# Pressure_ADC.net
KiCad netlist of a schematic drawn in Altium Designer
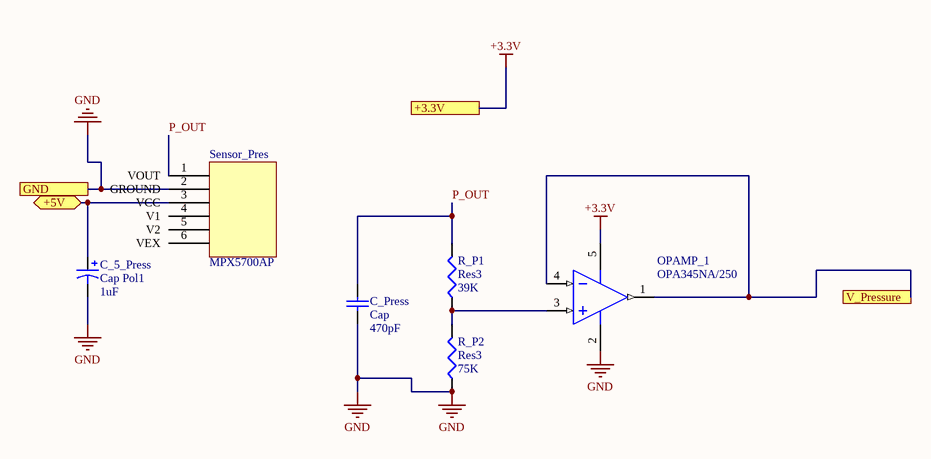
[diagram p0: Pressure ADC.SchDoc]

(export (version "E")
  (design (tool "Eeschema 10.0.6"))
  (components
    (comp (ref "C_5_Press")
      (value "Cap Pol1")
      (footprint "CAPR5-4X5")
      (description "Polarized Capacitor (Radial)")
      (fields (field (name "ALTIUM_VALUE") "1uF") (field (name "PUBLISHER") "Altium Limited"))
      (libsource (lib "Miscellaneous Devices") (part "Cap Pol1"))
    )
    (comp (ref "C_Press")
      (value "Cap")
      (footprint "3.2X1.6X1.1")
      (description "Capacitor")
      (fields (field (name "ALTIUM_VALUE") "470pF") (field (name "PUBLISHER") "Altium Limited"))
      (libsource (lib "Miscellaneous Devices") (part "Cap"))
    )
    (comp (ref "OPAMP_1")
      (value "OPA345NA/250")
      (footprint "TI-DBV5_N")
      (fields (field (name "MANUFACTURER") "Texas Instruments"))
      (libsource (lib "TI Amplifiers and Linear Operational Amplifier Precision Amplifier Part One") (part "OPA345NA/250"))
    )
    (comp (ref "R_P1")
      (value "Res3")
      (footprint "J1-0603")
      (description "Resistor")
      (fields (field (name "ALTIUM_VALUE") "39K") (field (name "PUBLISHER") "Altium Limited"))
      (libsource (lib "Miscellaneous Devices") (part "Res3"))
    )
    (comp (ref "R_P2")
      (value "Res3")
      (footprint "J1-0603")
      (description "Resistor")
      (fields (field (name "ALTIUM_VALUE") "75K") (field (name "PUBLISHER") "Altium Limited"))
      (libsource (lib "Miscellaneous Devices") (part "Res3"))
    )
    (comp (ref "Sensor_Pres")
      (value "MPX5700AP")
      (footprint "HDR1X6H")
      (libsource (lib "XSUB_COMP") (part "MPX5700AP"))
    )
  )
  (nets
    (net (code "1") (name "+3.3V") (class "Default")
      (node (ref "OPAMP_1") (pin "5") (pinfunction "V+_5") (pintype "power_in"))
    )
    (net (code "2") (name "/+5V") (class "Default")
      (node (ref "C_5_Press") (pin "1") (pinfunction "1_1") (pintype "passive"))
    )
    (net (code "3") (name "/P_OUT") (class "Default")
      (node (ref "C_Press") (pin "2") (pinfunction "2_2") (pintype "passive"))
      (node (ref "R_P1") (pin "2") (pinfunction "2_2") (pintype "passive"))
    )
    (net (code "4") (name "/V_Pressure") (class "Default")
      (node (ref "OPAMP_1") (pin "1") (pinfunction "OUT_1") (pintype "output"))
      (node (ref "OPAMP_1") (pin "4") (pinfunction "IN-_4") (pintype "input"))
    )
    (net (code "5") (name "GND") (class "Default")
      (node (ref "C_5_Press") (pin "2") (pinfunction "2_2") (pintype "passive"))
      (node (ref "C_Press") (pin "1") (pinfunction "1_1") (pintype "passive"))
      (node (ref "OPAMP_1") (pin "2") (pinfunction "V-_2") (pintype "power_in"))
      (node (ref "R_P2") (pin "1") (pinfunction "1_1") (pintype "passive"))
    )
    (net (code "6") (name "Net-(OPAMP_1-IN+)") (class "Default")
      (node (ref "OPAMP_1") (pin "3") (pinfunction "IN+_3") (pintype "input"))
      (node (ref "R_P1") (pin "1") (pinfunction "1_1") (pintype "passive"))
      (node (ref "R_P2") (pin "2") (pinfunction "2_2") (pintype "passive"))
    )
    (net (code "7") (name "unconnected-(Sensor_Pres-GROUND-Pad2)") (class "Default")
      (node (ref "Sensor_Pres") (pin "2") (pinfunction "GROUND_2") (pintype "passive"))
    )
    (net (code "8") (name "unconnected-(Sensor_Pres-V1-Pad4)") (class "Default")
      (node (ref "Sensor_Pres") (pin "4") (pinfunction "V1_4") (pintype "passive"))
    )
    (net (code "9") (name "unconnected-(Sensor_Pres-V2-Pad5)") (class "Default")
      (node (ref "Sensor_Pres") (pin "5") (pinfunction "V2_5") (pintype "passive"))
    )
    (net (code "10") (name "unconnected-(Sensor_Pres-VCC-Pad3)") (class "Default")
      (node (ref "Sensor_Pres") (pin "3") (pinfunction "VCC_3") (pintype "passive"))
    )
    (net (code "11") (name "unconnected-(Sensor_Pres-VEX-Pad6)") (class "Default")
      (node (ref "Sensor_Pres") (pin "6") (pinfunction "VEX_6") (pintype "passive"))
    )
    (net (code "12") (name "unconnected-(Sensor_Pres-VOUT-Pad1)") (class "Default")
      (node (ref "Sensor_Pres") (pin "1") (pinfunction "VOUT_1") (pintype "passive"))
    )
  )
)
